# relay.net
KiCad netlist of a schematic drawn in Altium Designer
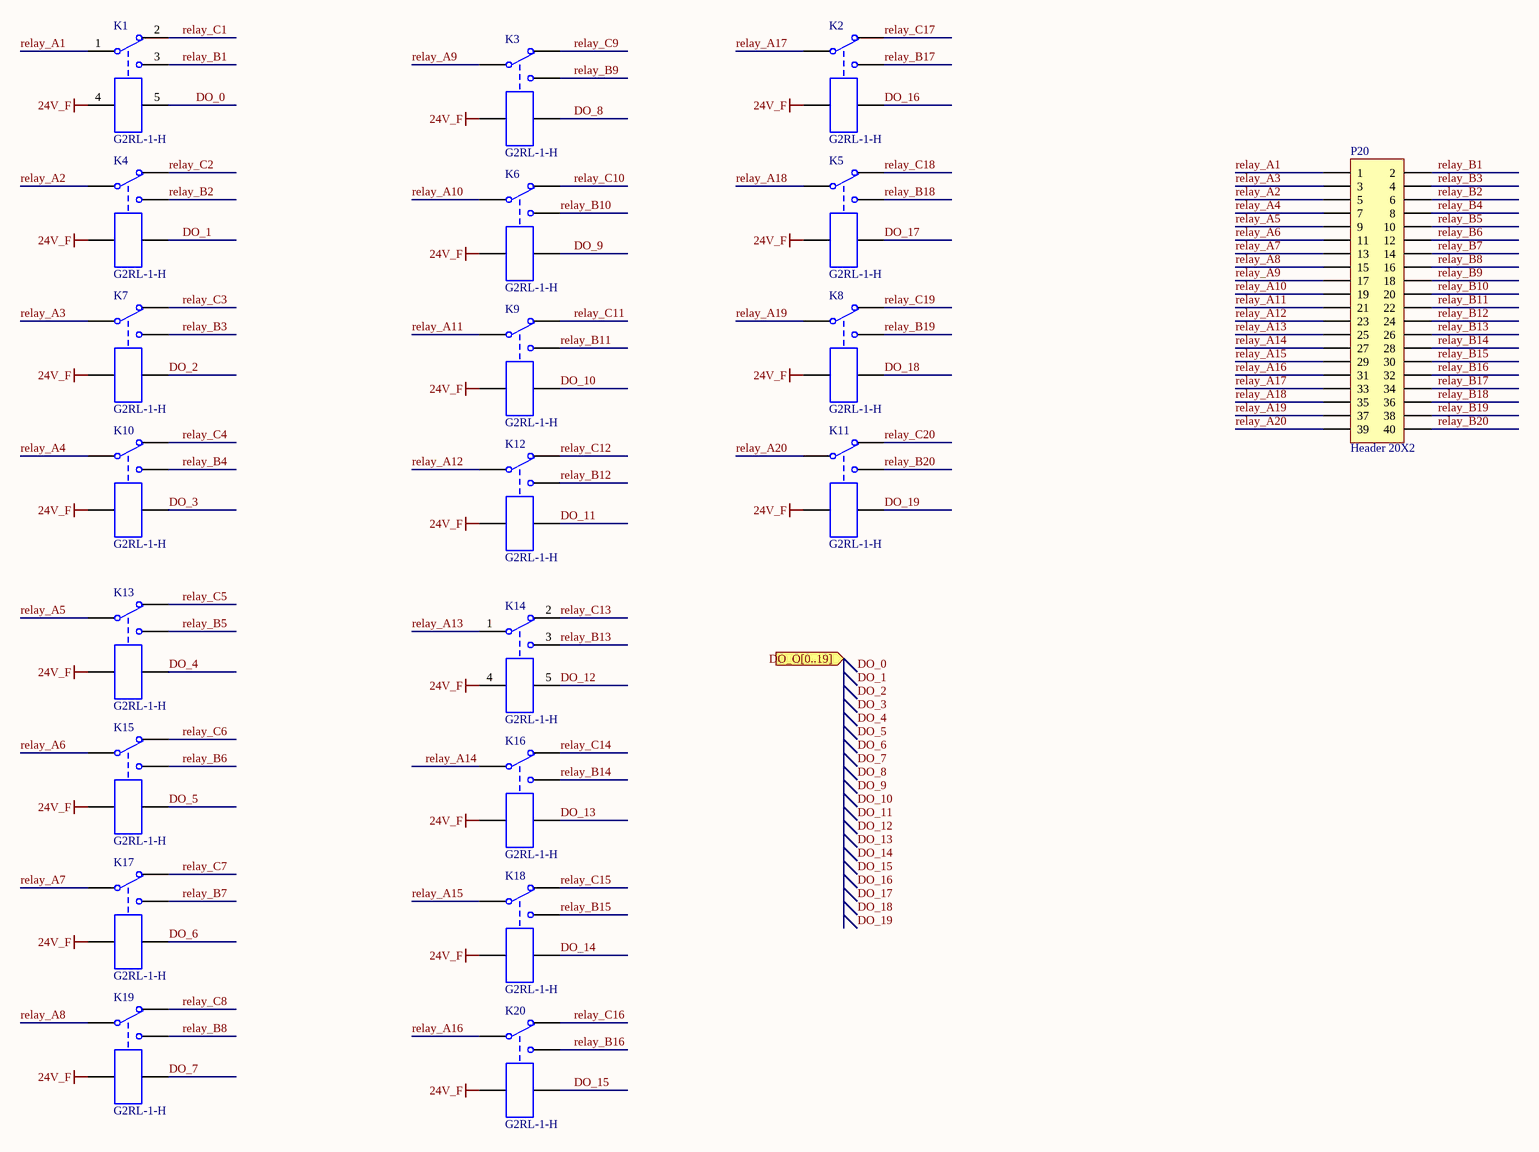
[diagram p0: relay.SchDoc]

(export (version "E")
  (design (tool "Eeschema 10.0.6"))
  (components
    (comp (ref "K1")
      (value "G2RL-1-H")
      (footprint "G2RL-1-H")
      (description "Single-Pole Dual-Throw Relay")
      (fields (field (name "PUBLISHER") "Altium Limited"))
      (libsource (lib "") (part "Relay-SPDT_1"))
    )
    (comp (ref "K2")
      (value "G2RL-1-H")
      (footprint "G2RL-1-H")
      (description "Single-Pole Dual-Throw Relay")
      (fields (field (name "PUBLISHER") "Altium Limited"))
      (libsource (lib "Miscellaneous Devices") (part "Relay-SPDT"))
    )
    (comp (ref "K3")
      (value "G2RL-1-H")
      (footprint "G2RL-1-H")
      (description "Single-Pole Dual-Throw Relay")
      (fields (field (name "PUBLISHER") "Altium Limited"))
      (libsource (lib "Miscellaneous Devices") (part "Relay-SPDT"))
    )
    (comp (ref "K4")
      (value "G2RL-1-H")
      (footprint "G2RL-1-H")
      (description "Single-Pole Dual-Throw Relay")
      (fields (field (name "PUBLISHER") "Altium Limited"))
      (libsource (lib "Miscellaneous Devices") (part "Relay-SPDT"))
    )
    (comp (ref "K5")
      (value "G2RL-1-H")
      (footprint "G2RL-1-H")
      (description "Single-Pole Dual-Throw Relay")
      (fields (field (name "PUBLISHER") "Altium Limited"))
      (libsource (lib "Miscellaneous Devices") (part "Relay-SPDT"))
    )
    (comp (ref "K6")
      (value "G2RL-1-H")
      (footprint "G2RL-1-H")
      (description "Single-Pole Dual-Throw Relay")
      (fields (field (name "PUBLISHER") "Altium Limited"))
      (libsource (lib "Miscellaneous Devices") (part "Relay-SPDT"))
    )
    (comp (ref "K7")
      (value "G2RL-1-H")
      (footprint "G2RL-1-H")
      (description "Single-Pole Dual-Throw Relay")
      (fields (field (name "PUBLISHER") "Altium Limited"))
      (libsource (lib "Miscellaneous Devices") (part "Relay-SPDT"))
    )
    (comp (ref "K8")
      (value "G2RL-1-H")
      (footprint "G2RL-1-H")
      (description "Single-Pole Dual-Throw Relay")
      (fields (field (name "PUBLISHER") "Altium Limited"))
      (libsource (lib "Miscellaneous Devices") (part "Relay-SPDT"))
    )
    (comp (ref "K9")
      (value "G2RL-1-H")
      (footprint "G2RL-1-H")
      (description "Single-Pole Dual-Throw Relay")
      (fields (field (name "PUBLISHER") "Altium Limited"))
      (libsource (lib "Miscellaneous Devices") (part "Relay-SPDT"))
    )
    (comp (ref "K10")
      (value "G2RL-1-H")
      (footprint "G2RL-1-H")
      (description "Single-Pole Dual-Throw Relay")
      (fields (field (name "PUBLISHER") "Altium Limited"))
      (libsource (lib "Miscellaneous Devices") (part "Relay-SPDT"))
    )
    (comp (ref "K11")
      (value "G2RL-1-H")
      (footprint "G2RL-1-H")
      (description "Single-Pole Dual-Throw Relay")
      (fields (field (name "PUBLISHER") "Altium Limited"))
      (libsource (lib "Miscellaneous Devices") (part "Relay-SPDT"))
    )
    (comp (ref "K12")
      (value "G2RL-1-H")
      (footprint "G2RL-1-H")
      (description "Single-Pole Dual-Throw Relay")
      (fields (field (name "PUBLISHER") "Altium Limited"))
      (libsource (lib "Miscellaneous Devices") (part "Relay-SPDT"))
    )
    (comp (ref "K13")
      (value "G2RL-1-H")
      (footprint "G2RL-1-H")
      (description "Single-Pole Dual-Throw Relay")
      (fields (field (name "PUBLISHER") "Altium Limited"))
      (libsource (lib "Miscellaneous Devices") (part "Relay-SPDT"))
    )
    (comp (ref "K14")
      (value "G2RL-1-H")
      (footprint "G2RL-1-H")
      (description "Single-Pole Dual-Throw Relay")
      (fields (field (name "PUBLISHER") "Altium Limited"))
      (libsource (lib "") (part "Relay-SPDT_1"))
    )
    (comp (ref "K15")
      (value "G2RL-1-H")
      (footprint "G2RL-1-H")
      (description "Single-Pole Dual-Throw Relay")
      (fields (field (name "PUBLISHER") "Altium Limited"))
      (libsource (lib "Miscellaneous Devices") (part "Relay-SPDT"))
    )
    (comp (ref "K16")
      (value "G2RL-1-H")
      (footprint "G2RL-1-H")
      (description "Single-Pole Dual-Throw Relay")
      (fields (field (name "PUBLISHER") "Altium Limited"))
      (libsource (lib "Miscellaneous Devices") (part "Relay-SPDT"))
    )
    (comp (ref "K17")
      (value "G2RL-1-H")
      (footprint "G2RL-1-H")
      (description "Single-Pole Dual-Throw Relay")
      (fields (field (name "PUBLISHER") "Altium Limited"))
      (libsource (lib "Miscellaneous Devices") (part "Relay-SPDT"))
    )
    (comp (ref "K18")
      (value "G2RL-1-H")
      (footprint "G2RL-1-H")
      (description "Single-Pole Dual-Throw Relay")
      (fields (field (name "PUBLISHER") "Altium Limited"))
      (libsource (lib "Miscellaneous Devices") (part "Relay-SPDT"))
    )
    (comp (ref "K19")
      (value "G2RL-1-H")
      (footprint "G2RL-1-H")
      (description "Single-Pole Dual-Throw Relay")
      (fields (field (name "PUBLISHER") "Altium Limited"))
      (libsource (lib "Miscellaneous Devices") (part "Relay-SPDT"))
    )
    (comp (ref "K20")
      (value "G2RL-1-H")
      (footprint "G2RL-1-H")
      (description "Single-Pole Dual-Throw Relay")
      (fields (field (name "PUBLISHER") "Altium Limited"))
      (libsource (lib "Miscellaneous Devices") (part "Relay-SPDT"))
    )
    (comp (ref "P20")
      (value "Header 20X2")
      (footprint "XH2.54_2x20")
      (description "Header, 20-Pin, Dual row")
      (fields (field (name "PUBLISHER") "Altium Limited"))
      (libsource (lib "Miscellaneous Connectors") (part "Header 20X2"))
    )
  )
  (nets
    (net (code "21") (name "/DO_0") (class "Default")
      (node (ref "K1") (pin "5") (pinfunction "5_5") (pintype "passive"))
    )
    (net (code "22") (name "/DO_1") (class "Default")
      (node (ref "K4") (pin "5") (pinfunction "5_5") (pintype "passive"))
    )
    (net (code "23") (name "/DO_2") (class "Default")
      (node (ref "K7") (pin "5") (pinfunction "5_5") (pintype "passive"))
    )
    (net (code "24") (name "/DO_3") (class "Default")
      (node (ref "K10") (pin "5") (pinfunction "5_5") (pintype "passive"))
    )
    (net (code "25") (name "/DO_4") (class "Default")
      (node (ref "K13") (pin "5") (pinfunction "5_5") (pintype "passive"))
    )
    (net (code "26") (name "/DO_5") (class "Default")
      (node (ref "K15") (pin "5") (pinfunction "5_5") (pintype "passive"))
    )
    (net (code "27") (name "/DO_6") (class "Default")
      (node (ref "K17") (pin "5") (pinfunction "5_5") (pintype "passive"))
    )
    (net (code "28") (name "/DO_7") (class "Default")
      (node (ref "K19") (pin "5") (pinfunction "5_5") (pintype "passive"))
    )
    (net (code "29") (name "/DO_8") (class "Default")
      (node (ref "K3") (pin "5") (pinfunction "5_5") (pintype "passive"))
    )
    (net (code "30") (name "/DO_9") (class "Default")
      (node (ref "K6") (pin "5") (pinfunction "5_5") (pintype "passive"))
    )
    (net (code "31") (name "/DO_10") (class "Default")
      (node (ref "K9") (pin "5") (pinfunction "5_5") (pintype "passive"))
    )
    (net (code "32") (name "/DO_11") (class "Default")
      (node (ref "K12") (pin "5") (pinfunction "5_5") (pintype "passive"))
    )
    (net (code "33") (name "/DO_12") (class "Default")
      (node (ref "K14") (pin "5") (pinfunction "5_5") (pintype "passive"))
    )
    (net (code "34") (name "/DO_13") (class "Default")
      (node (ref "K16") (pin "5") (pinfunction "5_5") (pintype "passive"))
    )
    (net (code "35") (name "/DO_14") (class "Default")
      (node (ref "K18") (pin "5") (pinfunction "5_5") (pintype "passive"))
    )
    (net (code "36") (name "/DO_15") (class "Default")
      (node (ref "K20") (pin "5") (pinfunction "5_5") (pintype "passive"))
    )
    (net (code "37") (name "/DO_16") (class "Default")
      (node (ref "K2") (pin "5") (pinfunction "5_5") (pintype "passive"))
    )
    (net (code "38") (name "/DO_17") (class "Default")
      (node (ref "K5") (pin "5") (pinfunction "5_5") (pintype "passive"))
    )
    (net (code "39") (name "/DO_18") (class "Default")
      (node (ref "K8") (pin "5") (pinfunction "5_5") (pintype "passive"))
    )
    (net (code "40") (name "/DO_19") (class "Default")
      (node (ref "K11") (pin "5") (pinfunction "5_5") (pintype "passive"))
    )
    (net (code "42") (name "/relay_A1") (class "Default")
      (node (ref "K1") (pin "1") (pinfunction "1_1") (pintype "passive"))
      (node (ref "P20") (pin "1") (pinfunction "1_1") (pintype "passive"))
    )
    (net (code "43") (name "/relay_A2") (class "Default")
      (node (ref "K4") (pin "1") (pinfunction "1_1") (pintype "passive"))
      (node (ref "P20") (pin "5") (pinfunction "5_5") (pintype "passive"))
    )
    (net (code "44") (name "/relay_A3") (class "Default")
      (node (ref "K7") (pin "1") (pinfunction "1_1") (pintype "passive"))
      (node (ref "P20") (pin "3") (pinfunction "3_3") (pintype "passive"))
    )
    (net (code "45") (name "/relay_A4") (class "Default")
      (node (ref "K10") (pin "1") (pinfunction "1_1") (pintype "passive"))
      (node (ref "P20") (pin "7") (pinfunction "7_7") (pintype "passive"))
    )
    (net (code "46") (name "/relay_A5") (class "Default")
      (node (ref "K13") (pin "1") (pinfunction "1_1") (pintype "passive"))
      (node (ref "P20") (pin "9") (pinfunction "9_9") (pintype "passive"))
    )
    (net (code "47") (name "/relay_A6") (class "Default")
      (node (ref "K15") (pin "1") (pinfunction "1_1") (pintype "passive"))
      (node (ref "P20") (pin "11") (pinfunction "11_11") (pintype "passive"))
    )
    (net (code "48") (name "/relay_A7") (class "Default")
      (node (ref "K17") (pin "1") (pinfunction "1_1") (pintype "passive"))
      (node (ref "P20") (pin "13") (pinfunction "13_13") (pintype "passive"))
    )
    (net (code "49") (name "/relay_A8") (class "Default")
      (node (ref "K19") (pin "1") (pinfunction "1_1") (pintype "passive"))
      (node (ref "P20") (pin "15") (pinfunction "15_15") (pintype "passive"))
    )
    (net (code "50") (name "/relay_A9") (class "Default")
      (node (ref "K3") (pin "1") (pinfunction "1_1") (pintype "passive"))
      (node (ref "P20") (pin "17") (pinfunction "17_17") (pintype "passive"))
    )
    (net (code "51") (name "/relay_A10") (class "Default")
      (node (ref "K6") (pin "1") (pinfunction "1_1") (pintype "passive"))
      (node (ref "P20") (pin "19") (pinfunction "19_19") (pintype "passive"))
    )
    (net (code "52") (name "/relay_A11") (class "Default")
      (node (ref "K9") (pin "1") (pinfunction "1_1") (pintype "passive"))
      (node (ref "P20") (pin "21") (pinfunction "21_21") (pintype "passive"))
    )
    (net (code "53") (name "/relay_A12") (class "Default")
      (node (ref "K12") (pin "1") (pinfunction "1_1") (pintype "passive"))
      (node (ref "P20") (pin "23") (pinfunction "23_23") (pintype "passive"))
    )
    (net (code "54") (name "/relay_A13") (class "Default")
      (node (ref "K14") (pin "1") (pinfunction "1_1") (pintype "passive"))
      (node (ref "P20") (pin "25") (pinfunction "25_25") (pintype "passive"))
    )
    (net (code "55") (name "/relay_A14") (class "Default")
      (node (ref "K16") (pin "1") (pinfunction "1_1") (pintype "passive"))
      (node (ref "P20") (pin "27") (pinfunction "27_27") (pintype "passive"))
    )
    (net (code "56") (name "/relay_A15") (class "Default")
      (node (ref "K18") (pin "1") (pinfunction "1_1") (pintype "passive"))
      (node (ref "P20") (pin "29") (pinfunction "29_29") (pintype "passive"))
    )
    (net (code "57") (name "/relay_A16") (class "Default")
      (node (ref "K20") (pin "1") (pinfunction "1_1") (pintype "passive"))
      (node (ref "P20") (pin "31") (pinfunction "31_31") (pintype "passive"))
    )
    (net (code "58") (name "/relay_A17") (class "Default")
      (node (ref "K2") (pin "1") (pinfunction "1_1") (pintype "passive"))
      (node (ref "P20") (pin "33") (pinfunction "33_33") (pintype "passive"))
    )
    (net (code "59") (name "/relay_A18") (class "Default")
      (node (ref "K5") (pin "1") (pinfunction "1_1") (pintype "passive"))
      (node (ref "P20") (pin "35") (pinfunction "35_35") (pintype "passive"))
    )
    (net (code "60") (name "/relay_A19") (class "Default")
      (node (ref "K8") (pin "1") (pinfunction "1_1") (pintype "passive"))
      (node (ref "P20") (pin "37") (pinfunction "37_37") (pintype "passive"))
    )
    (net (code "61") (name "/relay_A20") (class "Default")
      (node (ref "K11") (pin "1") (pinfunction "1_1") (pintype "passive"))
      (node (ref "P20") (pin "39") (pinfunction "39_39") (pintype "passive"))
    )
    (net (code "62") (name "/relay_B1") (class "Default")
      (node (ref "K1") (pin "3") (pinfunction "3_3") (pintype "passive"))
      (node (ref "P20") (pin "2") (pinfunction "2_2") (pintype "passive"))
    )
    (net (code "63") (name "/relay_B2") (class "Default")
      (node (ref "K4") (pin "3") (pinfunction "3_3") (pintype "passive"))
      (node (ref "P20") (pin "6") (pinfunction "6_6") (pintype "passive"))
    )
    (net (code "64") (name "/relay_B3") (class "Default")
      (node (ref "K7") (pin "3") (pinfunction "3_3") (pintype "passive"))
      (node (ref "P20") (pin "4") (pinfunction "4_4") (pintype "passive"))
    )
    (net (code "65") (name "/relay_B4") (class "Default")
      (node (ref "K10") (pin "3") (pinfunction "3_3") (pintype "passive"))
      (node (ref "P20") (pin "8") (pinfunction "8_8") (pintype "passive"))
    )
    (net (code "66") (name "/relay_B5") (class "Default")
      (node (ref "K13") (pin "3") (pinfunction "3_3") (pintype "passive"))
      (node (ref "P20") (pin "10") (pinfunction "10_10") (pintype "passive"))
    )
    (net (code "67") (name "/relay_B6") (class "Default")
      (node (ref "K15") (pin "3") (pinfunction "3_3") (pintype "passive"))
      (node (ref "P20") (pin "12") (pinfunction "12_12") (pintype "passive"))
    )
    (net (code "68") (name "/relay_B7") (class "Default")
      (node (ref "K17") (pin "3") (pinfunction "3_3") (pintype "passive"))
      (node (ref "P20") (pin "14") (pinfunction "14_14") (pintype "passive"))
    )
    (net (code "69") (name "/relay_B8") (class "Default")
      (node (ref "K19") (pin "3") (pinfunction "3_3") (pintype "passive"))
      (node (ref "P20") (pin "16") (pinfunction "16_16") (pintype "passive"))
    )
    (net (code "70") (name "/relay_B9") (class "Default")
      (node (ref "K3") (pin "3") (pinfunction "3_3") (pintype "passive"))
      (node (ref "P20") (pin "18") (pinfunction "18_18") (pintype "passive"))
    )
    (net (code "71") (name "/relay_B10") (class "Default")
      (node (ref "K6") (pin "3") (pinfunction "3_3") (pintype "passive"))
      (node (ref "P20") (pin "20") (pinfunction "20_20") (pintype "passive"))
    )
    (net (code "72") (name "/relay_B11") (class "Default")
      (node (ref "K9") (pin "3") (pinfunction "3_3") (pintype "passive"))
      (node (ref "P20") (pin "22") (pinfunction "22_22") (pintype "passive"))
    )
    (net (code "73") (name "/relay_B12") (class "Default")
      (node (ref "K12") (pin "3") (pinfunction "3_3") (pintype "passive"))
      (node (ref "P20") (pin "24") (pinfunction "24_24") (pintype "passive"))
    )
    (net (code "74") (name "/relay_B13") (class "Default")
      (node (ref "K14") (pin "3") (pinfunction "3_3") (pintype "passive"))
      (node (ref "P20") (pin "26") (pinfunction "26_26") (pintype "passive"))
    )
    (net (code "75") (name "/relay_B14") (class "Default")
      (node (ref "K16") (pin "3") (pinfunction "3_3") (pintype "passive"))
      (node (ref "P20") (pin "28") (pinfunction "28_28") (pintype "passive"))
    )
    (net (code "76") (name "/relay_B15") (class "Default")
      (node (ref "K18") (pin "3") (pinfunction "3_3") (pintype "passive"))
      (node (ref "P20") (pin "30") (pinfunction "30_30") (pintype "passive"))
    )
    (net (code "77") (name "/relay_B16") (class "Default")
      (node (ref "K20") (pin "3") (pinfunction "3_3") (pintype "passive"))
      (node (ref "P20") (pin "32") (pinfunction "32_32") (pintype "passive"))
    )
    (net (code "78") (name "/relay_B17") (class "Default")
      (node (ref "K2") (pin "3") (pinfunction "3_3") (pintype "passive"))
      (node (ref "P20") (pin "34") (pinfunction "34_34") (pintype "passive"))
    )
    (net (code "79") (name "/relay_B18") (class "Default")
      (node (ref "K5") (pin "3") (pinfunction "3_3") (pintype "passive"))
      (node (ref "P20") (pin "36") (pinfunction "36_36") (pintype "passive"))
    )
    (net (code "80") (name "/relay_B19") (class "Default")
      (node (ref "K8") (pin "3") (pinfunction "3_3") (pintype "passive"))
      (node (ref "P20") (pin "38") (pinfunction "38_38") (pintype "passive"))
    )
    (net (code "81") (name "/relay_B20") (class "Default")
      (node (ref "K11") (pin "3") (pinfunction "3_3") (pintype "passive"))
      (node (ref "P20") (pin "40") (pinfunction "40_40") (pintype "passive"))
    )
    (net (code "82") (name "/relay_C1") (class "Default")
      (node (ref "K1") (pin "2") (pinfunction "2_2") (pintype "passive"))
    )
    (net (code "83") (name "/relay_C2") (class "Default")
      (node (ref "K4") (pin "2") (pinfunction "2_2") (pintype "passive"))
    )
    (net (code "84") (name "/relay_C3") (class "Default")
      (node (ref "K7") (pin "2") (pinfunction "2_2") (pintype "passive"))
    )
    (net (code "85") (name "/relay_C4") (class "Default")
      (node (ref "K10") (pin "2") (pinfunction "2_2") (pintype "passive"))
    )
    (net (code "86") (name "/relay_C5") (class "Default")
      (node (ref "K13") (pin "2") (pinfunction "2_2") (pintype "passive"))
    )
    (net (code "87") (name "/relay_C6") (class "Default")
      (node (ref "K15") (pin "2") (pinfunction "2_2") (pintype "passive"))
    )
    (net (code "88") (name "/relay_C7") (class "Default")
      (node (ref "K17") (pin "2") (pinfunction "2_2") (pintype "passive"))
    )
    (net (code "89") (name "/relay_C8") (class "Default")
      (node (ref "K19") (pin "2") (pinfunction "2_2") (pintype "passive"))
    )
    (net (code "90") (name "/relay_C9") (class "Default")
      (node (ref "K3") (pin "2") (pinfunction "2_2") (pintype "passive"))
    )
    (net (code "91") (name "/relay_C10") (class "Default")
      (node (ref "K6") (pin "2") (pinfunction "2_2") (pintype "passive"))
    )
    (net (code "92") (name "/relay_C11") (class "Default")
      (node (ref "K9") (pin "2") (pinfunction "2_2") (pintype "passive"))
    )
    (net (code "93") (name "/relay_C12") (class "Default")
      (node (ref "K12") (pin "2") (pinfunction "2_2") (pintype "passive"))
    )
    (net (code "94") (name "/relay_C13") (class "Default")
      (node (ref "K14") (pin "2") (pinfunction "2_2") (pintype "passive"))
    )
    (net (code "95") (name "/relay_C14") (class "Default")
      (node (ref "K16") (pin "2") (pinfunction "2_2") (pintype "passive"))
    )
    (net (code "96") (name "/relay_C15") (class "Default")
      (node (ref "K18") (pin "2") (pinfunction "2_2") (pintype "passive"))
    )
    (net (code "97") (name "/relay_C16") (class "Default")
      (node (ref "K20") (pin "2") (pinfunction "2_2") (pintype "passive"))
    )
    (net (code "98") (name "/relay_C17") (class "Default")
      (node (ref "K2") (pin "2") (pinfunction "2_2") (pintype "passive"))
    )
    (net (code "99") (name "/relay_C18") (class "Default")
      (node (ref "K5") (pin "2") (pinfunction "2_2") (pintype "passive"))
    )
    (net (code "100") (name "/relay_C19") (class "Default")
      (node (ref "K8") (pin "2") (pinfunction "2_2") (pintype "passive"))
    )
    (net (code "101") (name "/relay_C20") (class "Default")
      (node (ref "K11") (pin "2") (pinfunction "2_2") (pintype "passive"))
    )
    (net (code "102") (name "24V_F") (class "Default")
      (node (ref "K1") (pin "4") (pinfunction "4_4") (pintype "passive"))
      (node (ref "K10") (pin "4") (pinfunction "4_4") (pintype "passive"))
      (node (ref "K11") (pin "4") (pinfunction "4_4") (pintype "passive"))
      (node (ref "K12") (pin "4") (pinfunction "4_4") (pintype "passive"))
      (node (ref "K13") (pin "4") (pinfunction "4_4") (pintype "passive"))
      (node (ref "K14") (pin "4") (pinfunction "4_4") (pintype "passive"))
      (node (ref "K15") (pin "4") (pinfunction "4_4") (pintype "passive"))
      (node (ref "K16") (pin "4") (pinfunction "4_4") (pintype "passive"))
      (node (ref "K17") (pin "4") (pinfunction "4_4") (pintype "passive"))
      (node (ref "K18") (pin "4") (pinfunction "4_4") (pintype "passive"))
      (node (ref "K19") (pin "4") (pinfunction "4_4") (pintype "passive"))
      (node (ref "K2") (pin "4") (pinfunction "4_4") (pintype "passive"))
      (node (ref "K20") (pin "4") (pinfunction "4_4") (pintype "passive"))
      (node (ref "K3") (pin "4") (pinfunction "4_4") (pintype "passive"))
      (node (ref "K4") (pin "4") (pinfunction "4_4") (pintype "passive"))
      (node (ref "K5") (pin "4") (pinfunction "4_4") (pintype "passive"))
      (node (ref "K6") (pin "4") (pinfunction "4_4") (pintype "passive"))
      (node (ref "K7") (pin "4") (pinfunction "4_4") (pintype "passive"))
      (node (ref "K8") (pin "4") (pinfunction "4_4") (pintype "passive"))
      (node (ref "K9") (pin "4") (pinfunction "4_4") (pintype "passive"))
    )
  )
)
